# board.net
KiCad netlist of a schematic drawn in EAGLE
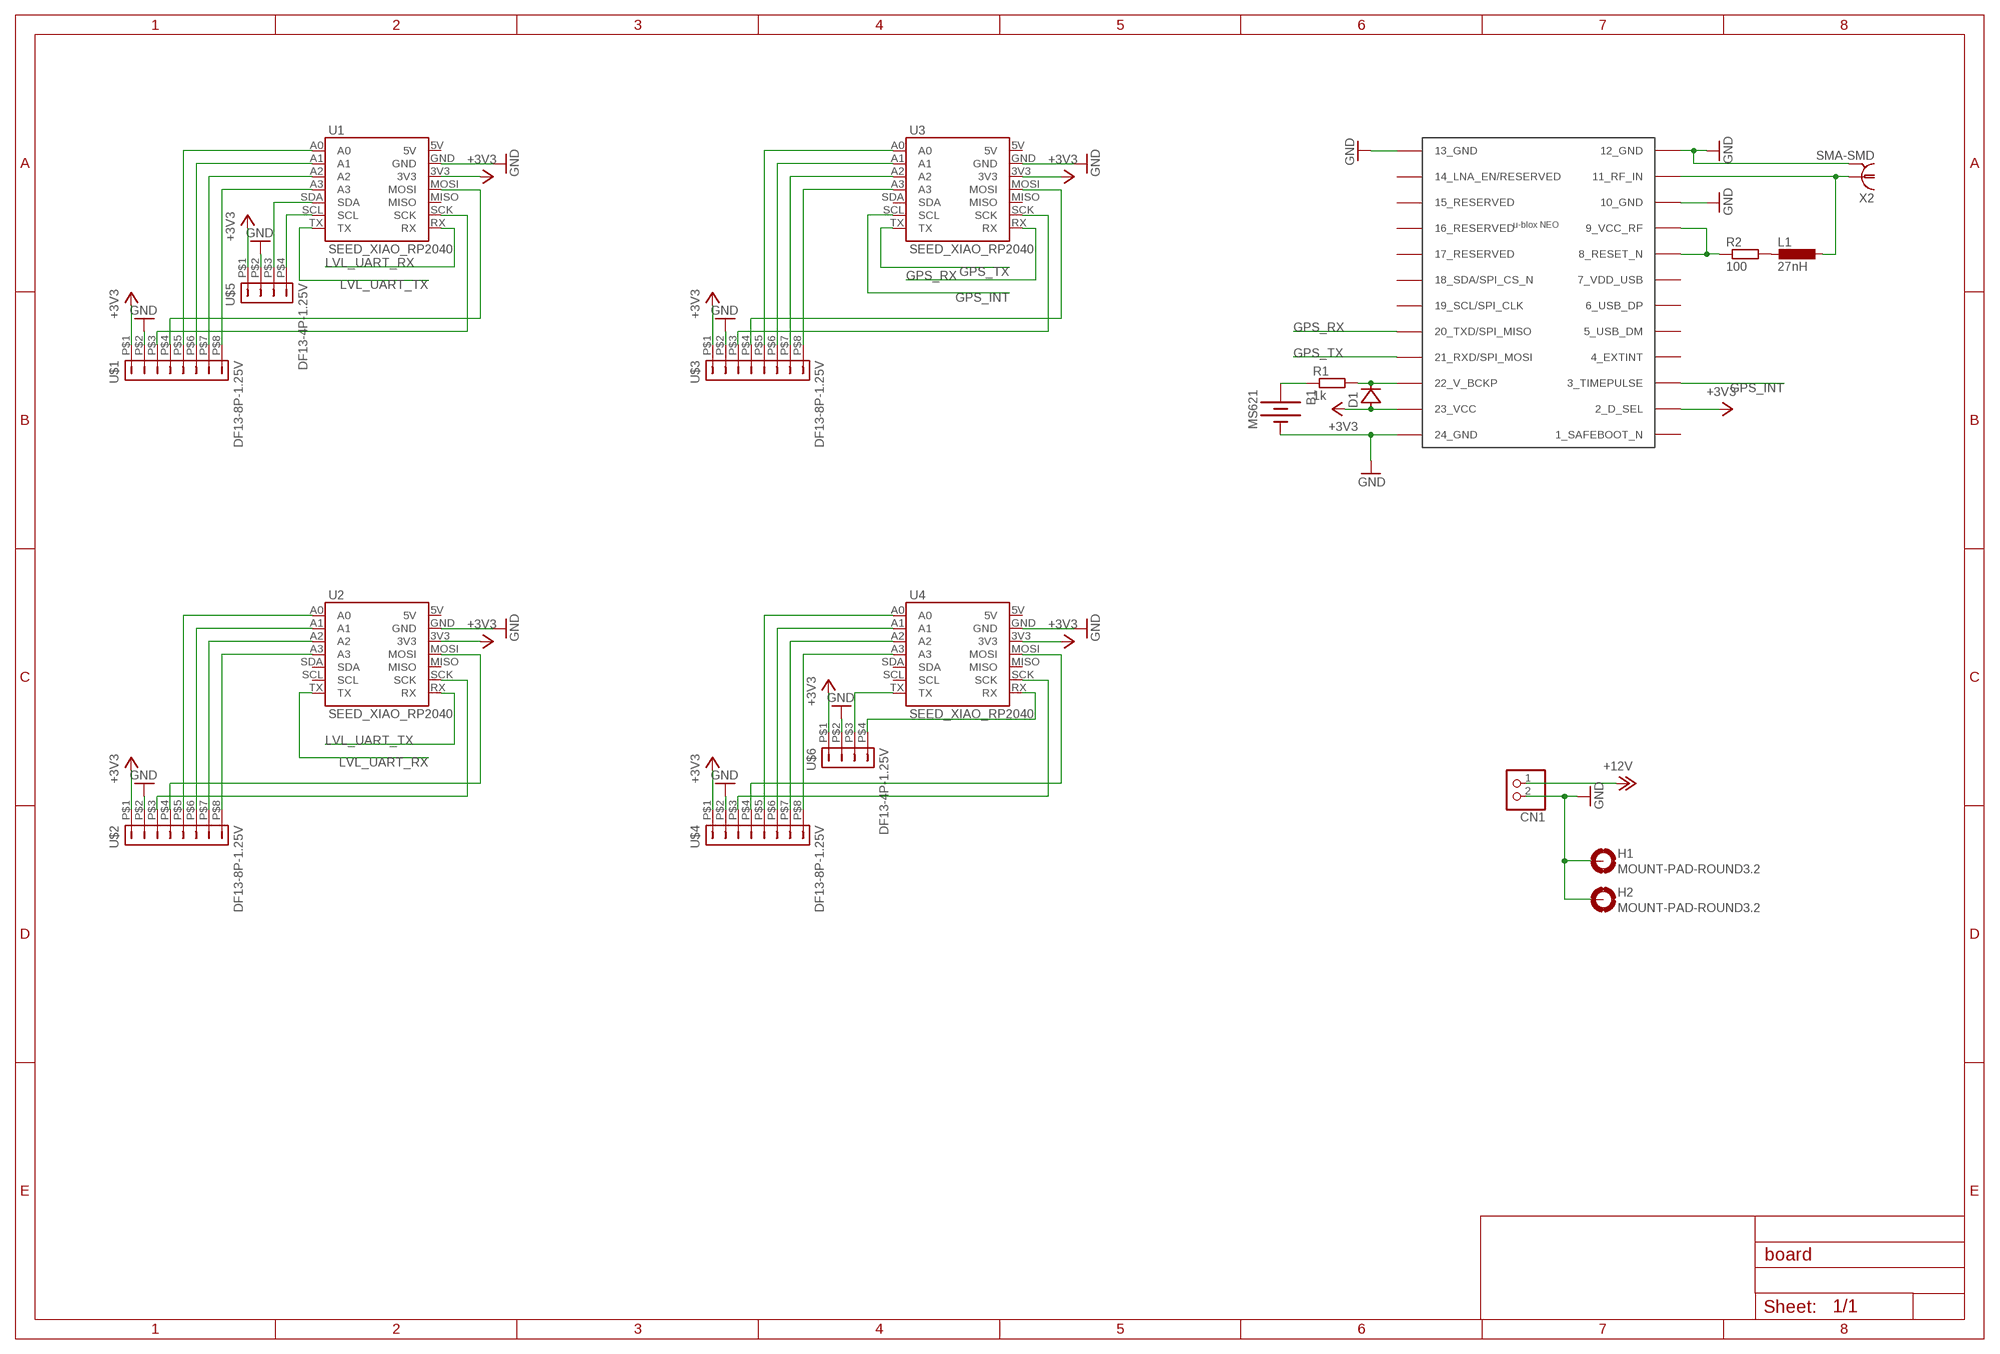
[diagram p0: schematic, sheet 1]

(export (version "E")
  (design (tool "Eeschema 10.0.6"))
  (components
    (comp (ref "B1")
      (value "MS621")
      (footprint "eagle-import:MS621FE-IL36E")
      (libsource (lib "eagle-import") (part "MS621"))
    )
    (comp (ref "CN1")
      (value "JST_2PIN-SMT-RA")
      (footprint "eagle-import:JST-PH-2-SMT-RA")
      (libsource (lib "eagle-import") (part "JST_2PIN-SMT-RA"))
    )
    (comp (ref "D1")
      (value "DIODESOD-123")
      (footprint "eagle-import:SOD123")
      (libsource (lib "eagle-import") (part "DIODESOD-123"))
    )
    (comp (ref "H1")
      (value "MOUNT-PAD-ROUND3.2")
      (footprint "eagle-import:3,2-PAD")
      (libsource (lib "eagle-import") (part "MOUNT-PAD-ROUND3.2"))
    )
    (comp (ref "H2")
      (value "MOUNT-PAD-ROUND3.2")
      (footprint "eagle-import:3,2-PAD")
      (libsource (lib "eagle-import") (part "MOUNT-PAD-ROUND3.2"))
    )
    (comp (ref "L1")
      (value "27nH")
      (footprint "eagle-import:L2012C")
      (libsource (lib "eagle-import") (part "INDUCTOR0805"))
    )
    (comp (ref "R1")
      (value "1k")
      (footprint "eagle-import:R0805")
      (libsource (lib "eagle-import") (part "RESISTOR0805"))
    )
    (comp (ref "R2")
      (value "100")
      (footprint "eagle-import:R0805")
      (libsource (lib "eagle-import") (part "RESISTOR0805"))
    )
    (comp (ref "U$1")
      (value "DF13-8P-1.25V")
      (footprint "eagle-import:DF13C-8P-1.25V")
      (libsource (lib "eagle-import") (part "DF13-8P-1.25V"))
    )
    (comp (ref "U$2")
      (value "DF13-8P-1.25V")
      (footprint "eagle-import:DF13C-8P-1.25V")
      (libsource (lib "eagle-import") (part "DF13-8P-1.25V"))
    )
    (comp (ref "U$3")
      (value "DF13-8P-1.25V")
      (footprint "eagle-import:DF13C-8P-1.25V")
      (libsource (lib "eagle-import") (part "DF13-8P-1.25V"))
    )
    (comp (ref "U$4")
      (value "DF13-8P-1.25V")
      (footprint "eagle-import:DF13C-8P-1.25V")
      (libsource (lib "eagle-import") (part "DF13-8P-1.25V"))
    )
    (comp (ref "U$5")
      (value "DF13-4P-1.25V")
      (footprint "eagle-import:DF13C-4P-1.25V")
      (libsource (lib "eagle-import") (part "DF13-4P-1.25V"))
    )
    (comp (ref "U$6")
      (value "DF13-4P-1.25V")
      (footprint "eagle-import:DF13C-4P-1.25V")
      (libsource (lib "eagle-import") (part "DF13-4P-1.25V"))
    )
    (comp (ref "U$7")
      (value "NEO-M8")
      (footprint "eagle-import:NEO-M8")
      (libsource (lib "eagle-import") (part "NEO-M8"))
    )
    (comp (ref "U1")
      (value "SEED_XIAO_RP2040")
      (footprint "eagle-import:SEED_XIAO_RP2040")
      (libsource (lib "eagle-import") (part "SEED_XIAO_RP2040"))
    )
    (comp (ref "U2")
      (value "SEED_XIAO_RP2040")
      (footprint "eagle-import:SEED_XIAO_RP2040")
      (libsource (lib "eagle-import") (part "SEED_XIAO_RP2040"))
    )
    (comp (ref "U3")
      (value "SEED_XIAO_RP2040")
      (footprint "eagle-import:SEED_XIAO_RP2040")
      (libsource (lib "eagle-import") (part "SEED_XIAO_RP2040"))
    )
    (comp (ref "U4")
      (value "SEED_XIAO_RP2040")
      (footprint "eagle-import:SEED_XIAO_RP2040")
      (libsource (lib "eagle-import") (part "SEED_XIAO_RP2040"))
    )
    (comp (ref "X2")
      (value "SMA-SMD")
      (footprint "eagle-import:SMA-SMD")
      (libsource (lib "eagle-import") (part "SMA-SMD"))
    )
  )
  (nets
    (net (code "1") (name "+3V3") (class "Default")
      (node (ref "D1") (pin "A") (pinfunction "A_A") (pintype "passive"))
      (node (ref "U$1") (pin "P$1") (pinfunction "1_P$1") (pintype "passive"))
      (node (ref "U$2") (pin "P$1") (pinfunction "1_P$1") (pintype "passive"))
      (node (ref "U$3") (pin "P$1") (pinfunction "1_P$1") (pintype "passive"))
      (node (ref "U$4") (pin "P$1") (pinfunction "1_P$1") (pintype "passive"))
      (node (ref "U$5") (pin "P$1") (pinfunction "1_P$1") (pintype "passive"))
      (node (ref "U$6") (pin "P$1") (pinfunction "1_P$1") (pintype "passive"))
      (node (ref "U$7") (pin "2") (pinfunction "2_D_SEL_2") (pintype "bidirectional"))
      (node (ref "U$7") (pin "23") (pinfunction "23_VCC_23") (pintype "bidirectional"))
      (node (ref "U1") (pin "3V3") (pinfunction "3V3_3V3") (pintype "bidirectional"))
      (node (ref "U2") (pin "3V3") (pinfunction "3V3_3V3") (pintype "bidirectional"))
      (node (ref "U3") (pin "3V3") (pinfunction "3V3_3V3") (pintype "bidirectional"))
      (node (ref "U4") (pin "3V3") (pinfunction "3V3_3V3") (pintype "bidirectional"))
    )
    (net (code "2") (name "+12V") (class "Default")
      (node (ref "CN1") (pin "1") (pinfunction "2_1") (pintype "passive"))
    )
    (net (code "3") (name "/GPS_INT") (class "Default")
      (node (ref "U$7") (pin "3") (pinfunction "3_TIMEPULSE_3") (pintype "bidirectional"))
      (node (ref "U3") (pin "SCL") (pinfunction "SCL_SCL") (pintype "bidirectional"))
    )
    (net (code "4") (name "/GPS_RX") (class "Default")
      (node (ref "U$7") (pin "20") (pinfunction "20_TXD/SPI_MISO_20") (pintype "bidirectional"))
      (node (ref "U3") (pin "RX") (pinfunction "RX_RX") (pintype "bidirectional"))
    )
    (net (code "5") (name "/GPS_TX") (class "Default")
      (node (ref "U$7") (pin "21") (pinfunction "21_RXD/SPI_MOSI_21") (pintype "bidirectional"))
      (node (ref "U3") (pin "TX") (pinfunction "TX_TX") (pintype "bidirectional"))
    )
    (net (code "6") (name "/LVL_UART_RX") (class "Default")
      (node (ref "U1") (pin "RX") (pinfunction "RX_RX") (pintype "bidirectional"))
      (node (ref "U2") (pin "TX") (pinfunction "TX_TX") (pintype "bidirectional"))
    )
    (net (code "7") (name "/LVL_UART_TX") (class "Default")
      (node (ref "U1") (pin "TX") (pinfunction "TX_TX") (pintype "bidirectional"))
      (node (ref "U2") (pin "RX") (pinfunction "RX_RX") (pintype "bidirectional"))
    )
    (net (code "8") (name "GND") (class "Default")
      (node (ref "B1") (pin "P$1") (pinfunction "-_P$1") (pintype "power_in"))
      (node (ref "CN1") (pin "2") (pinfunction "1_2") (pintype "passive"))
      (node (ref "H1") (pin "B3,2") (pinfunction "MOUNT_B3,2") (pintype "passive"))
      (node (ref "H1") (pin "P$1") (pinfunction "MOUNT_P$1") (pintype "passive"))
      (node (ref "H1") (pin "P$2") (pinfunction "MOUNT_P$2") (pintype "passive"))
      (node (ref "H1") (pin "P$3") (pinfunction "MOUNT_P$3") (pintype "passive"))
      (node (ref "H1") (pin "P$4") (pinfunction "MOUNT_P$4") (pintype "passive"))
      (node (ref "H1") (pin "P$5") (pinfunction "MOUNT_P$5") (pintype "passive"))
      (node (ref "H1") (pin "P$6") (pinfunction "MOUNT_P$6") (pintype "passive"))
      (node (ref "H1") (pin "P$7") (pinfunction "MOUNT_P$7") (pintype "passive"))
      (node (ref "H1") (pin "P$8") (pinfunction "MOUNT_P$8") (pintype "passive"))
      (node (ref "H2") (pin "B3,2") (pinfunction "MOUNT_B3,2") (pintype "passive"))
      (node (ref "H2") (pin "P$1") (pinfunction "MOUNT_P$1") (pintype "passive"))
      (node (ref "H2") (pin "P$2") (pinfunction "MOUNT_P$2") (pintype "passive"))
      (node (ref "H2") (pin "P$3") (pinfunction "MOUNT_P$3") (pintype "passive"))
      (node (ref "H2") (pin "P$4") (pinfunction "MOUNT_P$4") (pintype "passive"))
      (node (ref "H2") (pin "P$5") (pinfunction "MOUNT_P$5") (pintype "passive"))
      (node (ref "H2") (pin "P$6") (pinfunction "MOUNT_P$6") (pintype "passive"))
      (node (ref "H2") (pin "P$7") (pinfunction "MOUNT_P$7") (pintype "passive"))
      (node (ref "H2") (pin "P$8") (pinfunction "MOUNT_P$8") (pintype "passive"))
      (node (ref "U$1") (pin "P$2") (pinfunction "2_P$2") (pintype "passive"))
      (node (ref "U$2") (pin "P$2") (pinfunction "2_P$2") (pintype "passive"))
      (node (ref "U$3") (pin "P$2") (pinfunction "2_P$2") (pintype "passive"))
      (node (ref "U$4") (pin "P$2") (pinfunction "2_P$2") (pintype "passive"))
      (node (ref "U$5") (pin "P$2") (pinfunction "2_P$2") (pintype "passive"))
      (node (ref "U$6") (pin "P$2") (pinfunction "2_P$2") (pintype "passive"))
      (node (ref "U$7") (pin "10") (pinfunction "10_GND_10") (pintype "bidirectional"))
      (node (ref "U$7") (pin "12") (pinfunction "12_GND_12") (pintype "bidirectional"))
      (node (ref "U$7") (pin "13") (pinfunction "13_GND_13") (pintype "bidirectional"))
      (node (ref "U$7") (pin "24") (pinfunction "24_GND_24") (pintype "bidirectional"))
      (node (ref "U1") (pin "GND") (pinfunction "GND_GND") (pintype "bidirectional"))
      (node (ref "U2") (pin "GND") (pinfunction "GND_GND") (pintype "bidirectional"))
      (node (ref "U3") (pin "GND") (pinfunction "GND_GND") (pintype "bidirectional"))
      (node (ref "U4") (pin "GND") (pinfunction "GND_GND") (pintype "bidirectional"))
      (node (ref "X2") (pin "2@1") (pinfunction "2_2@1") (pintype "passive"))
      (node (ref "X2") (pin "2@2") (pinfunction "2_2@2") (pintype "passive"))
      (node (ref "X2") (pin "2@3") (pinfunction "2_2@3") (pintype "passive"))
      (node (ref "X2") (pin "2@4") (pinfunction "2_2@4") (pintype "passive"))
      (node (ref "X2") (pin "2@5") (pinfunction "2_2@5") (pintype "passive"))
      (node (ref "X2") (pin "2@6") (pinfunction "2_2@6") (pintype "passive"))
    )
    (net (code "9") (name "Net-(B1-+)") (class "Default")
      (node (ref "B1") (pin "P$2") (pinfunction "+_P$2") (pintype "power_in"))
      (node (ref "R1") (pin "1") (pinfunction "1_1") (pintype "passive"))
    )
    (net (code "10") (name "Net-(L1-Pad2)") (class "Default")
      (node (ref "L1") (pin "2") (pinfunction "2_2") (pintype "passive"))
      (node (ref "R2") (pin "2") (pinfunction "2_2") (pintype "passive"))
    )
    (net (code "11") (name "Net-(U$1-3)") (class "Default")
      (node (ref "U$1") (pin "P$3") (pinfunction "3_P$3") (pintype "passive"))
      (node (ref "U1") (pin "SCK") (pinfunction "SCK_SCK") (pintype "bidirectional"))
    )
    (net (code "12") (name "Net-(U$1-4)") (class "Default")
      (node (ref "U$1") (pin "P$4") (pinfunction "4_P$4") (pintype "passive"))
      (node (ref "U1") (pin "MOSI") (pinfunction "MOSI_MOSI") (pintype "bidirectional"))
    )
    (net (code "13") (name "Net-(U$1-5)") (class "Default")
      (node (ref "U$1") (pin "P$5") (pinfunction "5_P$5") (pintype "passive"))
      (node (ref "U1") (pin "A0") (pinfunction "A0_A0") (pintype "bidirectional"))
    )
    (net (code "14") (name "Net-(U$1-6)") (class "Default")
      (node (ref "U$1") (pin "P$6") (pinfunction "6_P$6") (pintype "passive"))
      (node (ref "U1") (pin "A1") (pinfunction "A1_A1") (pintype "bidirectional"))
    )
    (net (code "15") (name "Net-(U$1-7)") (class "Default")
      (node (ref "U$1") (pin "P$7") (pinfunction "7_P$7") (pintype "passive"))
      (node (ref "U1") (pin "A2") (pinfunction "A2_A2") (pintype "bidirectional"))
    )
    (net (code "16") (name "Net-(U$1-8)") (class "Default")
      (node (ref "U$1") (pin "P$8") (pinfunction "8_P$8") (pintype "passive"))
      (node (ref "U1") (pin "A3") (pinfunction "A3_A3") (pintype "bidirectional"))
    )
    (net (code "17") (name "Net-(U$2-3)") (class "Default")
      (node (ref "U$2") (pin "P$3") (pinfunction "3_P$3") (pintype "passive"))
      (node (ref "U2") (pin "SCK") (pinfunction "SCK_SCK") (pintype "bidirectional"))
    )
    (net (code "18") (name "Net-(U$2-4)") (class "Default")
      (node (ref "U$2") (pin "P$4") (pinfunction "4_P$4") (pintype "passive"))
      (node (ref "U2") (pin "MOSI") (pinfunction "MOSI_MOSI") (pintype "bidirectional"))
    )
    (net (code "19") (name "Net-(U$2-5)") (class "Default")
      (node (ref "U$2") (pin "P$5") (pinfunction "5_P$5") (pintype "passive"))
      (node (ref "U2") (pin "A0") (pinfunction "A0_A0") (pintype "bidirectional"))
    )
    (net (code "20") (name "Net-(U$2-6)") (class "Default")
      (node (ref "U$2") (pin "P$6") (pinfunction "6_P$6") (pintype "passive"))
      (node (ref "U2") (pin "A1") (pinfunction "A1_A1") (pintype "bidirectional"))
    )
    (net (code "21") (name "Net-(U$2-7)") (class "Default")
      (node (ref "U$2") (pin "P$7") (pinfunction "7_P$7") (pintype "passive"))
      (node (ref "U2") (pin "A2") (pinfunction "A2_A2") (pintype "bidirectional"))
    )
    (net (code "22") (name "Net-(U$2-8)") (class "Default")
      (node (ref "U$2") (pin "P$8") (pinfunction "8_P$8") (pintype "passive"))
      (node (ref "U2") (pin "A3") (pinfunction "A3_A3") (pintype "bidirectional"))
    )
    (net (code "23") (name "Net-(U$3-3)") (class "Default")
      (node (ref "U$3") (pin "P$3") (pinfunction "3_P$3") (pintype "passive"))
      (node (ref "U3") (pin "SCK") (pinfunction "SCK_SCK") (pintype "bidirectional"))
    )
    (net (code "24") (name "Net-(U$3-4)") (class "Default")
      (node (ref "U$3") (pin "P$4") (pinfunction "4_P$4") (pintype "passive"))
      (node (ref "U3") (pin "MOSI") (pinfunction "MOSI_MOSI") (pintype "bidirectional"))
    )
    (net (code "25") (name "Net-(U$3-5)") (class "Default")
      (node (ref "U$3") (pin "P$5") (pinfunction "5_P$5") (pintype "passive"))
      (node (ref "U3") (pin "A0") (pinfunction "A0_A0") (pintype "bidirectional"))
    )
    (net (code "26") (name "Net-(U$3-6)") (class "Default")
      (node (ref "U$3") (pin "P$6") (pinfunction "6_P$6") (pintype "passive"))
      (node (ref "U3") (pin "A1") (pinfunction "A1_A1") (pintype "bidirectional"))
    )
    (net (code "27") (name "Net-(U$3-7)") (class "Default")
      (node (ref "U$3") (pin "P$7") (pinfunction "7_P$7") (pintype "passive"))
      (node (ref "U3") (pin "A2") (pinfunction "A2_A2") (pintype "bidirectional"))
    )
    (net (code "28") (name "Net-(U$3-8)") (class "Default")
      (node (ref "U$3") (pin "P$8") (pinfunction "8_P$8") (pintype "passive"))
      (node (ref "U3") (pin "A3") (pinfunction "A3_A3") (pintype "bidirectional"))
    )
    (net (code "29") (name "Net-(U$4-3)") (class "Default")
      (node (ref "U$4") (pin "P$3") (pinfunction "3_P$3") (pintype "passive"))
      (node (ref "U4") (pin "SCK") (pinfunction "SCK_SCK") (pintype "bidirectional"))
    )
    (net (code "30") (name "Net-(U$4-4)") (class "Default")
      (node (ref "U$4") (pin "P$4") (pinfunction "4_P$4") (pintype "passive"))
      (node (ref "U4") (pin "MOSI") (pinfunction "MOSI_MOSI") (pintype "bidirectional"))
    )
    (net (code "31") (name "Net-(U$4-5)") (class "Default")
      (node (ref "U$4") (pin "P$5") (pinfunction "5_P$5") (pintype "passive"))
      (node (ref "U4") (pin "A0") (pinfunction "A0_A0") (pintype "bidirectional"))
    )
    (net (code "32") (name "Net-(U$4-6)") (class "Default")
      (node (ref "U$4") (pin "P$6") (pinfunction "6_P$6") (pintype "passive"))
      (node (ref "U4") (pin "A1") (pinfunction "A1_A1") (pintype "bidirectional"))
    )
    (net (code "33") (name "Net-(U$4-7)") (class "Default")
      (node (ref "U$4") (pin "P$7") (pinfunction "7_P$7") (pintype "passive"))
      (node (ref "U4") (pin "A2") (pinfunction "A2_A2") (pintype "bidirectional"))
    )
    (net (code "34") (name "Net-(U$4-8)") (class "Default")
      (node (ref "U$4") (pin "P$8") (pinfunction "8_P$8") (pintype "passive"))
      (node (ref "U4") (pin "A3") (pinfunction "A3_A3") (pintype "bidirectional"))
    )
    (net (code "35") (name "Net-(U$5-3)") (class "Default")
      (node (ref "U$5") (pin "P$3") (pinfunction "3_P$3") (pintype "passive"))
      (node (ref "U1") (pin "SDA") (pinfunction "SDA_SDA") (pintype "bidirectional"))
    )
    (net (code "36") (name "Net-(U$5-4)") (class "Default")
      (node (ref "U$5") (pin "P$4") (pinfunction "4_P$4") (pintype "passive"))
      (node (ref "U1") (pin "SCL") (pinfunction "SCL_SCL") (pintype "bidirectional"))
    )
    (net (code "37") (name "Net-(U$6-3)") (class "Default")
      (node (ref "U$6") (pin "P$3") (pinfunction "3_P$3") (pintype "passive"))
      (node (ref "U4") (pin "TX") (pinfunction "TX_TX") (pintype "bidirectional"))
    )
    (net (code "38") (name "Net-(U$6-4)") (class "Default")
      (node (ref "U$6") (pin "P$4") (pinfunction "4_P$4") (pintype "passive"))
      (node (ref "U4") (pin "RX") (pinfunction "RX_RX") (pintype "bidirectional"))
    )
    (net (code "39") (name "Net-(U$7-8_RESET_N)") (class "Default")
      (node (ref "R2") (pin "1") (pinfunction "1_1") (pintype "passive"))
      (node (ref "U$7") (pin "8") (pinfunction "8_RESET_N_8") (pintype "bidirectional"))
      (node (ref "U$7") (pin "9") (pinfunction "9_VCC_RF_9") (pintype "bidirectional"))
    )
    (net (code "40") (name "Net-(U$7-11_RF_IN)") (class "Default")
      (node (ref "L1") (pin "1") (pinfunction "1_1") (pintype "passive"))
      (node (ref "U$7") (pin "11") (pinfunction "11_RF_IN_11") (pintype "bidirectional"))
      (node (ref "X2") (pin "1") (pinfunction "1_1") (pintype "passive"))
    )
    (net (code "41") (name "Net-(U$7-22_V_BCKP)") (class "Default")
      (node (ref "D1") (pin "C") (pinfunction "C_C") (pintype "passive"))
      (node (ref "R1") (pin "2") (pinfunction "2_2") (pintype "passive"))
      (node (ref "U$7") (pin "22") (pinfunction "22_V_BCKP_22") (pintype "bidirectional"))
    )
    (net (code "42") (name "unconnected-(U$7-1_SAFEBOOT_N-Pad1)") (class "Default")
      (node (ref "U$7") (pin "1") (pinfunction "1_SAFEBOOT_N_1") (pintype "bidirectional"))
    )
    (net (code "43") (name "unconnected-(U$7-4_EXTINT-Pad4)") (class "Default")
      (node (ref "U$7") (pin "4") (pinfunction "4_EXTINT_4") (pintype "bidirectional"))
    )
    (net (code "44") (name "unconnected-(U$7-5_USB_DM-Pad5)") (class "Default")
      (node (ref "U$7") (pin "5") (pinfunction "5_USB_DM_5") (pintype "bidirectional"))
    )
    (net (code "45") (name "unconnected-(U$7-6_USB_DP-Pad6)") (class "Default")
      (node (ref "U$7") (pin "6") (pinfunction "6_USB_DP_6") (pintype "bidirectional"))
    )
    (net (code "46") (name "unconnected-(U$7-7_VDD_USB-Pad7)") (class "Default")
      (node (ref "U$7") (pin "7") (pinfunction "7_VDD_USB_7") (pintype "bidirectional"))
    )
    (net (code "47") (name "unconnected-(U$7-14_LNA_EN{slash}RESERVED-Pad14)") (class "Default")
      (node (ref "U$7") (pin "14") (pinfunction "14_LNA_EN/RESERVED_14") (pintype "bidirectional"))
    )
    (net (code "48") (name "unconnected-(U$7-15_RESERVED-Pad15)") (class "Default")
      (node (ref "U$7") (pin "15") (pinfunction "15_RESERVED_15") (pintype "bidirectional"))
    )
    (net (code "49") (name "unconnected-(U$7-16_RESERVED-Pad16)") (class "Default")
      (node (ref "U$7") (pin "16") (pinfunction "16_RESERVED_16") (pintype "bidirectional"))
    )
    (net (code "50") (name "unconnected-(U$7-17_RESERVED-Pad17)") (class "Default")
      (node (ref "U$7") (pin "17") (pinfunction "17_RESERVED_17") (pintype "bidirectional"))
    )
    (net (code "51") (name "unconnected-(U$7-18_SDA{slash}SPI_CS_N-Pad18)") (class "Default")
      (node (ref "U$7") (pin "18") (pinfunction "18_SDA/SPI_CS_N_18") (pintype "bidirectional"))
    )
    (net (code "52") (name "unconnected-(U$7-19_SCL{slash}SPI_CLK-Pad19)") (class "Default")
      (node (ref "U$7") (pin "19") (pinfunction "19_SCL/SPI_CLK_19") (pintype "bidirectional"))
    )
    (net (code "53") (name "unconnected-(U1-Pad5V)") (class "Default")
      (node (ref "U1") (pin "5V") (pinfunction "5V_5V") (pintype "bidirectional"))
    )
    (net (code "54") (name "unconnected-(U1-PadMISO)") (class "Default")
      (node (ref "U1") (pin "MISO") (pinfunction "MISO_MISO") (pintype "bidirectional"))
    )
    (net (code "55") (name "unconnected-(U2-Pad5V)") (class "Default")
      (node (ref "U2") (pin "5V") (pinfunction "5V_5V") (pintype "bidirectional"))
    )
    (net (code "56") (name "unconnected-(U2-PadMISO)") (class "Default")
      (node (ref "U2") (pin "MISO") (pinfunction "MISO_MISO") (pintype "bidirectional"))
    )
    (net (code "57") (name "unconnected-(U2-PadSCL)") (class "Default")
      (node (ref "U2") (pin "SCL") (pinfunction "SCL_SCL") (pintype "bidirectional"))
    )
    (net (code "58") (name "unconnected-(U2-PadSDA)") (class "Default")
      (node (ref "U2") (pin "SDA") (pinfunction "SDA_SDA") (pintype "bidirectional"))
    )
    (net (code "59") (name "unconnected-(U3-Pad5V)") (class "Default")
      (node (ref "U3") (pin "5V") (pinfunction "5V_5V") (pintype "bidirectional"))
    )
    (net (code "60") (name "unconnected-(U3-PadMISO)") (class "Default")
      (node (ref "U3") (pin "MISO") (pinfunction "MISO_MISO") (pintype "bidirectional"))
    )
    (net (code "61") (name "unconnected-(U3-PadSDA)") (class "Default")
      (node (ref "U3") (pin "SDA") (pinfunction "SDA_SDA") (pintype "bidirectional"))
    )
    (net (code "62") (name "unconnected-(U4-Pad5V)") (class "Default")
      (node (ref "U4") (pin "5V") (pinfunction "5V_5V") (pintype "bidirectional"))
    )
    (net (code "63") (name "unconnected-(U4-PadMISO)") (class "Default")
      (node (ref "U4") (pin "MISO") (pinfunction "MISO_MISO") (pintype "bidirectional"))
    )
    (net (code "64") (name "unconnected-(U4-PadSCL)") (class "Default")
      (node (ref "U4") (pin "SCL") (pinfunction "SCL_SCL") (pintype "bidirectional"))
    )
    (net (code "65") (name "unconnected-(U4-PadSDA)") (class "Default")
      (node (ref "U4") (pin "SDA") (pinfunction "SDA_SDA") (pintype "bidirectional"))
    )
  )
)
